# untitled.net
KiCad netlist of a schematic drawn in EAGLE
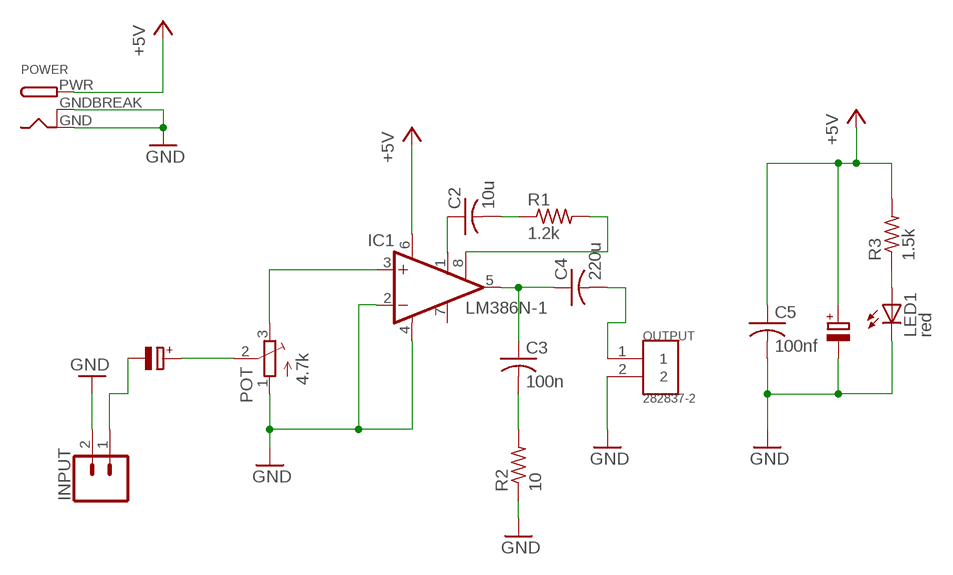
[diagram p0: schematic, sheet 1]

(export (version "E")
  (design (tool "Eeschema 10.0.6"))
  (components
    (comp (ref "C2")
      (value "10u")
      (footprint "eagle-import:C025-040X050")
      (libsource (lib "eagle-import") (part "C-US025-040X050"))
    )
    (comp (ref "C3")
      (value "100n")
      (footprint "eagle-import:C025-040X050")
      (libsource (lib "eagle-import") (part "C-US025-040X050"))
    )
    (comp (ref "C4")
      (value "220u")
      (footprint "eagle-import:C025-040X050")
      (libsource (lib "eagle-import") (part "C-US025-040X050"))
    )
    (comp (ref "C5")
      (value "100nf")
      (footprint "eagle-import:C025-040X050")
      (libsource (lib "eagle-import") (part "C-US025-040X050"))
    )
    (comp (ref "IC1")
      (value "LM386N-1")
      (footprint "eagle-import:DIL08")
      (libsource (lib "eagle-import") (part "LM386?-N1"))
    )
    (comp (ref "INPUT")
      (value "CONN_02")
      (footprint "eagle-import:1X02")
      (libsource (lib "eagle-import") (part "CONN_02"))
    )
    (comp (ref "LED1")
      (value "red")
      (footprint "eagle-import:LED3MM")
      (libsource (lib "eagle-import") (part "LED3MM"))
    )
    (comp (ref "OUTPUT")
      (value "282837-2")
      (footprint "eagle-import:TE_282837-2")
      (fields (field (name "MF") "TE Connectivity"))
      (libsource (lib "eagle-import") (part "282837-2"))
    )
    (comp (ref "POT")
      (value "4.7k")
      (footprint "eagle-import:TRIM-3386")
      (libsource (lib "eagle-import") (part "TRIMPOT3386"))
    )
    (comp (ref "POWER")
      (value "DCBARRELPTH")
      (footprint "eagle-import:DCJACK_2MM_PTH")
      (libsource (lib "eagle-import") (part "DCBARRELPTH"))
    )
    (comp (ref "R1")
      (value "1.2k")
      (footprint "eagle-import:0204_5")
      (libsource (lib "eagle-import") (part "R-US_0204/5"))
    )
    (comp (ref "R2")
      (value "10")
      (footprint "eagle-import:0204_5")
      (libsource (lib "eagle-import") (part "R-US_0204/5"))
    )
    (comp (ref "R3")
      (value "1.5k")
      (footprint "eagle-import:0204_5")
      (libsource (lib "eagle-import") (part "R-US_0204/5"))
    )
  )
  (nets
    (net (code "1") (name "+5V") (class "Default")
      (node (ref "C5") (pin "1") (pinfunction "1_1") (pintype "passive"))
      (node (ref "IC1") (pin "6") (pinfunction "VS_6") (pintype "power_in"))
      (node (ref "POWER") (pin "PWR") (pinfunction "PWR_PWR") (pintype "power_in"))
      (node (ref "R3") (pin "2") (pinfunction "2_2") (pintype "passive"))
    )
    (net (code "2") (name "GND") (class "Default")
      (node (ref "C5") (pin "2") (pinfunction "2_2") (pintype "passive"))
      (node (ref "IC1") (pin "2") (pinfunction "-IN_2") (pintype "input"))
      (node (ref "IC1") (pin "4") (pinfunction "GND_4") (pintype "power_in"))
      (node (ref "INPUT") (pin "2") (pinfunction "2_2") (pintype "passive"))
      (node (ref "LED1") (pin "K") (pinfunction "C_K") (pintype "passive"))
      (node (ref "OUTPUT") (pin "2") (pinfunction "2_2") (pintype "passive"))
      (node (ref "POT") (pin "1") (pinfunction "A_1") (pintype "passive"))
      (node (ref "POWER") (pin "GND") (pinfunction "GND_GND") (pintype "power_in"))
      (node (ref "POWER") (pin "GNDBREAK") (pinfunction "GNDBREAK_GNDBREAK") (pintype "power_in"))
      (node (ref "R2") (pin "1") (pinfunction "1_1") (pintype "passive"))
    )
    (net (code "3") (name "Net-(C2-Pad1)") (class "Default")
      (node (ref "C2") (pin "1") (pinfunction "1_1") (pintype "passive"))
      (node (ref "IC1") (pin "1") (pinfunction "GAIN_1") (pintype "passive"))
    )
    (net (code "4") (name "Net-(C2-Pad2)") (class "Default")
      (node (ref "C2") (pin "2") (pinfunction "2_2") (pintype "passive"))
      (node (ref "R1") (pin "1") (pinfunction "1_1") (pintype "passive"))
    )
    (net (code "5") (name "Net-(C3-Pad2)") (class "Default")
      (node (ref "C3") (pin "2") (pinfunction "2_2") (pintype "passive"))
      (node (ref "R2") (pin "2") (pinfunction "2_2") (pintype "passive"))
    )
    (net (code "6") (name "Net-(C4-Pad2)") (class "Default")
      (node (ref "C4") (pin "2") (pinfunction "2_2") (pintype "passive"))
      (node (ref "OUTPUT") (pin "1") (pinfunction "1_1") (pintype "passive"))
    )
    (net (code "7") (name "Net-(IC1-+IN)") (class "Default")
      (node (ref "IC1") (pin "3") (pinfunction "+IN_3") (pintype "input"))
      (node (ref "POT") (pin "3") (pinfunction "E_3") (pintype "passive"))
    )
    (net (code "8") (name "Net-(IC1-GAIN-Pad8)") (class "Default")
      (node (ref "IC1") (pin "8") (pinfunction "GAIN_8") (pintype "passive"))
      (node (ref "R1") (pin "2") (pinfunction "2_2") (pintype "passive"))
    )
    (net (code "9") (name "Net-(IC1-OUT)") (class "Default")
      (node (ref "C3") (pin "1") (pinfunction "1_1") (pintype "passive"))
      (node (ref "C4") (pin "1") (pinfunction "1_1") (pintype "passive"))
      (node (ref "IC1") (pin "5") (pinfunction "OUT_5") (pintype "output"))
    )
    (net (code "10") (name "Net-(LED1-PadA)") (class "Default")
      (node (ref "LED1") (pin "A") (pinfunction "A_A") (pintype "passive"))
      (node (ref "R3") (pin "1") (pinfunction "1_1") (pintype "passive"))
    )
    (net (code "11") (name "unconnected-(IC1-BYPASS-Pad7)") (class "Default")
      (node (ref "IC1") (pin "7") (pinfunction "BYPASS_7") (pintype "passive"))
    )
    (net (code "12") (name "unconnected-(INPUT-Pad1)") (class "Default")
      (node (ref "INPUT") (pin "1") (pinfunction "1_1") (pintype "passive"))
    )
    (net (code "13") (name "unconnected-(POT-S-Pad2)") (class "Default")
      (node (ref "POT") (pin "2") (pinfunction "S_2") (pintype "passive"))
    )
  )
)
